# 12_CONSOLE.net
KiCad netlist of a schematic drawn in Altium Designer
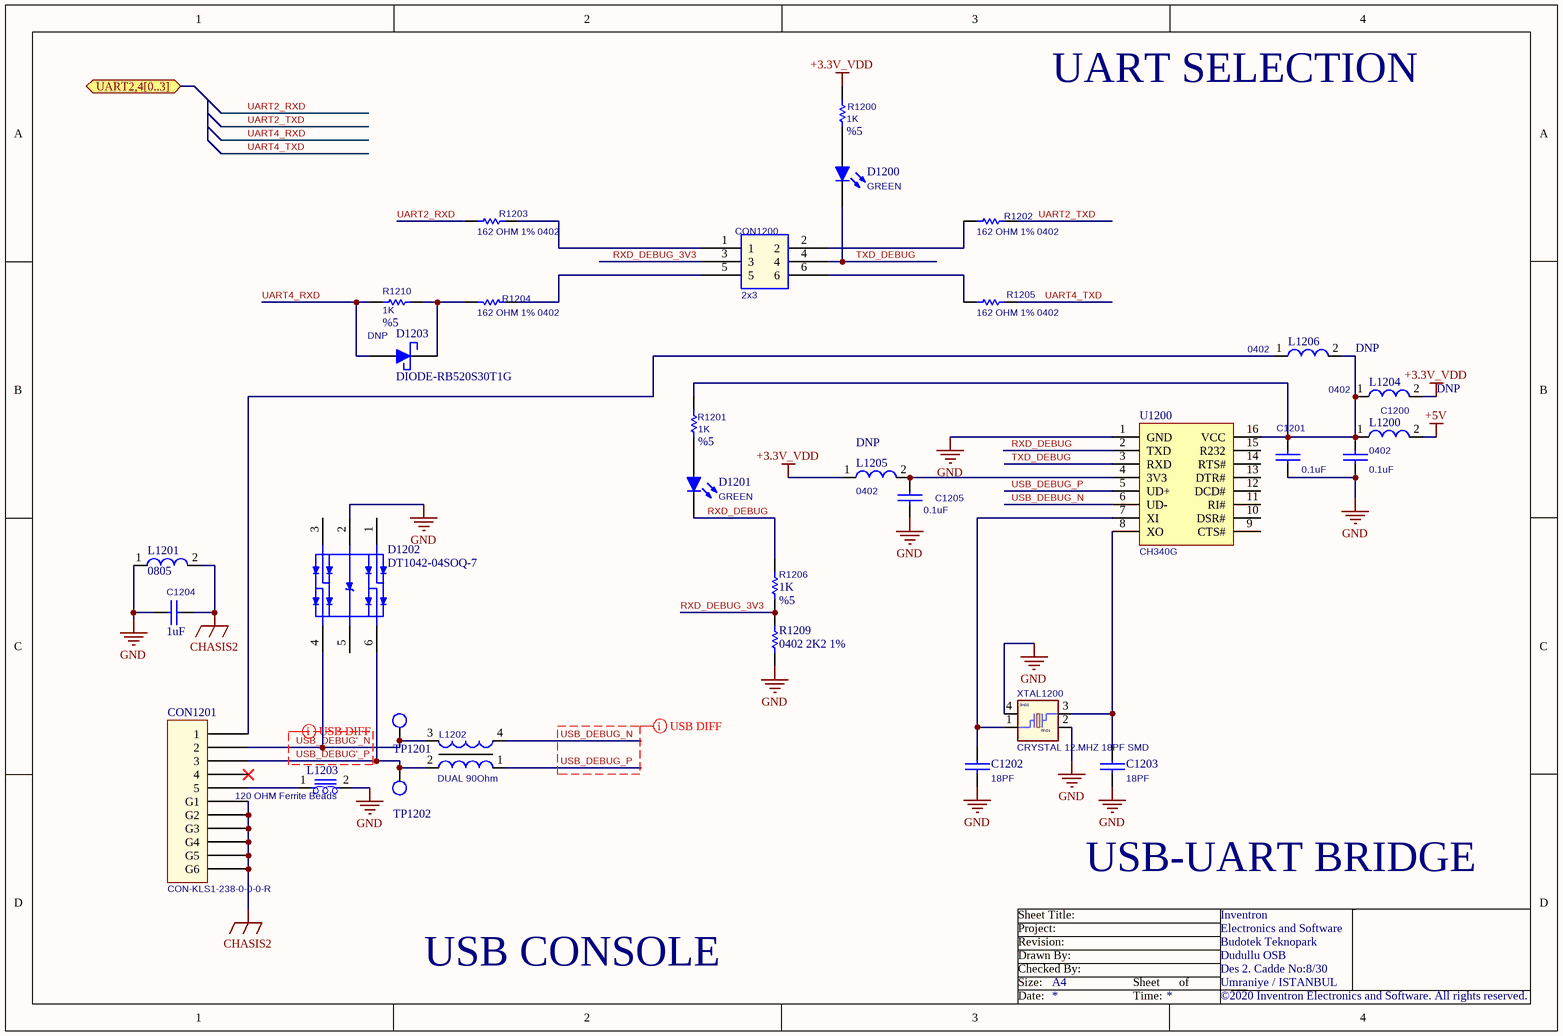
[diagram p0: 12 CONSOLE.SchDoc]

(export (version "E")
  (design (tool "Eeschema 10.0.6"))
  (components
    (comp (ref "C1200")
      (value "0.1uF")
      (footprint "0402_CC")
      (description "CAP VER 0.1UF 16V X7R 0402")
      (fields (field (name "CREATED BY") "LA") (field (name "CHECKED BY") "*"))
      (libsource (lib "ARETE_L") (part "CAP-CL05B104KO5NNNC"))
    )
    (comp (ref "C1201")
      (value "0.1uF")
      (footprint "0402_CC")
      (description "CAP VER 0.1UF 16V X7R 0402")
      (fields (field (name "CREATED BY") "LA") (field (name "CHECKED BY") "*"))
      (libsource (lib "ARETE_L") (part "CAP-CL05B104KO5NNNC"))
    )
    (comp (ref "C1202")
      (value "18PF")
      (footprint "0402_CC")
      (description "CAP CER 18PF 50V C0G/NP0 0402")
      (fields (field (name "CREATED BY") "*") (field (name "CHECKED BY") "*"))
      (libsource (lib "ARETE_SCH") (part "CAP-GCM1555C1H180JA16D"))
    )
    (comp (ref "C1203")
      (value "18PF")
      (footprint "0402_CC")
      (description "CAP CER 18PF 50V C0G/NP0 0402")
      (fields (field (name "CREATED BY") "*") (field (name "CHECKED BY") "*"))
      (libsource (lib "ARETE_SCH") (part "CAP-GCM1555C1H180JA16D"))
    )
    (comp (ref "C1204")
      (value "1uF")
      (footprint "0603_CC")
      (description "CAP CER 1UF 25V X7R 0603")
      (fields (field (name "CREATED BY") "LA") (field (name "CHECKED BY") "*"))
      (libsource (lib "ARETE_SCH") (part "CAP-CL10B105KA8NNNC"))
    )
    (comp (ref "C1205")
      (value "0.1uF")
      (footprint "0402_CC")
      (description "CAP VER 0.1UF 16V X7R 0402")
      (fields (field (name "CREATED BY") "LA") (field (name "CHECKED BY") "*"))
      (libsource (lib "ARETE_L") (part "CAP-CL05B104KO5NNNC"))
    )
    (comp (ref "CON1200")
      (value "2x3")
      (footprint "HEADER 2.54 X 3x2")
      (description "2x3 6 PIN 2.54MM HEADER")
      (fields (field (name "CREATED BY") "*") (field (name "CHECKED BY") "*"))
      (libsource (lib "ARETE_SCH") (part "CON-6 PIN 2.54MM"))
    )
    (comp (ref "CON1201")
      (value "CON-KLS1-238-0-0-0-R")
      (footprint "KLS1-238-0-0-0-R")
      (fields (field (name "CREATED BY") "OKS,EE") (field (name "CHECKED BY") "*"))
      (libsource (lib "ARETE_SCH") (part "CON-KLS1-238-0-0-0-R"))
    )
    (comp (ref "D1200")
      (value "GREEN")
      (footprint "0603_LED")
      (description "LED SMD 0603 SUPER GREEN")
      (fields (field (name "CREATED BY") "*") (field (name "CHECKED BY") "*"))
      (libsource (lib "ARETE_SCH") (part "LED-LTST-C190KRKT"))
    )
    (comp (ref "D1201")
      (value "GREEN")
      (footprint "0603_LED")
      (description "LED SMD 0603 SUPER GREEN")
      (fields (field (name "CREATED BY") "*") (field (name "CHECKED BY") "*"))
      (libsource (lib "ARETE_SCH") (part "LED-LTST-C190KRKT"))
    )
    (comp (ref "D1202")
      (value "DT1042-04SOQ-7")
      (footprint "DIODE-DT1042-04SOQ-7")
      (description "HDMI TVS DIODE")
      (fields (field (name "CREATED BY") "E.E") (field (name "CHECKED BY") "*"))
      (libsource (lib "ARETE_SCH") (part "DIODE-DT1042-04SOQ-7"))
    )
    (comp (ref "D1203")
      (value "DIODE-RB520S30T1G")
      (footprint "SOD523")
      (description "DIODE SCHOTTKY 30V 200MA SOD523")
      (fields (field (name "CREATED BY") "LA") (field (name "CHECKED BY") "*"))
      (libsource (lib "ARETE_L") (part "DIODE-RB520S30T1G"))
    )
    (comp (ref "L1200")
      (value "0402")
      (footprint "0402_RES")
      (description "0OHM 0402")
      (fields (field (name "CREATED BY") "EE") (field (name "CHECKED BY") "*"))
      (libsource (lib "ARETE_SCH") (part "IND-FERRITE (RES 0 OHM) 0402"))
    )
    (comp (ref "L1201")
      (value "0805")
      (footprint "0805")
      (description "0OHM 0805")
      (fields (field (name "CREATED BY") "EE") (field (name "CHECKED BY") "*"))
      (libsource (lib "ARETE_SCH") (part "IND-FERRITE (RES 0 OHM) 0805"))
    )
    (comp (ref "L1202")
      (value "DUAL 90Ohm")
      (footprint "DLW21H")
      (description "Common Mode Chokes Dual 90Ohm 100MHz 0.33A 0.35Ohm DCR SMD T/R")
      (fields (field (name "CREATED BY") "E.E") (field (name "CHECKED BY") "*"))
      (libsource (lib "ARETE_SCH") (part "IND-DLW21HN900SQ2L"))
    )
    (comp (ref "L1203")
      (value "120 OHM Ferrite Beads")
      (footprint "0603_RES")
      (description "Ferrite Beads Multi-Layer 120Ohm 25% 100MHz 2A 0.05Ohm DCR 0603 Automotive T/R")
      (fields (field (name "CREATED BY") "E.E") (field (name "CHECKED BY") "*"))
      (libsource (lib "ARETE_SCH") (part "IND-BLM18PG121SH1D"))
    )
    (comp (ref "L1204")
      (value "0402")
      (footprint "0402_RES")
      (description "0OHM 0402")
      (fields
        (field (name "ASSY_OPT") "DNP")
        (field (name "CREATED BY") "EE")
        (field (name "CHECKED BY") "*")
      )
      (libsource (lib "ARETE_SCH") (part "IND-FERRITE (RES 0 OHM) 0402"))
    )
    (comp (ref "L1205")
      (value "0402")
      (footprint "0402_RES")
      (description "0OHM 0402")
      (fields
        (field (name "ASSY_OPT") "DNP")
        (field (name "CREATED BY") "EE")
        (field (name "CHECKED BY") "*")
      )
      (libsource (lib "ARETE_SCH") (part "IND-FERRITE (RES 0 OHM) 0402"))
    )
    (comp (ref "L1206")
      (value "0402")
      (footprint "0402_RES")
      (description "0OHM 0402")
      (fields
        (field (name "ASSY_OPT") "DNP")
        (field (name "CREATED BY") "EE")
        (field (name "CHECKED BY") "*")
      )
      (libsource (lib "ARETE_SCH") (part "IND-FERRITE (RES 0 OHM) 0402"))
    )
    (comp (ref "R1200")
      (value "1K")
      (footprint "0402_RES")
      (description "RES 1K OHM 5% 1/16W 0402")
      (fields
        (field (name "TOLERANCE") "%5")
        (field (name "CREATED BY") "LA")
        (field (name "CHECKED BY") "*")
      )
      (libsource (lib "ARETE_SCH") (part "RES-RMCF0402JT1K00"))
    )
    (comp (ref "R1201")
      (value "1K")
      (footprint "0402_RES")
      (description "RES 1K OHM 5% 1/16W 0402")
      (fields
        (field (name "TOLERANCE") "%5")
        (field (name "CREATED BY") "LA")
        (field (name "CHECKED BY") "*")
      )
      (libsource (lib "ARETE_SCH") (part "RES-RMCF0402JT1K00"))
    )
    (comp (ref "R1202")
      (value "162 OHM 1% 0402")
      (footprint "0402_RES")
      (description "162 ±1% 0.1W, 1/10W Chip Resistor 0402 (1005 Metric) Automotive AEC-Q200 Thick Film")
      (fields (field (name "CREATED BY") "E.E") (field (name "CHECKED BY") "*"))
      (libsource (lib "ARETE_SCH") (part "RES-ERJ-2RKF1620X"))
    )
    (comp (ref "R1203")
      (value "162 OHM 1% 0402")
      (footprint "0402_RES")
      (description "162 ±1% 0.1W, 1/10W Chip Resistor 0402 (1005 Metric) Automotive AEC-Q200 Thick Film")
      (fields (field (name "CREATED BY") "E.E") (field (name "CHECKED BY") "*"))
      (libsource (lib "ARETE_SCH") (part "RES-ERJ-2RKF1620X"))
    )
    (comp (ref "R1204")
      (value "162 OHM 1% 0402")
      (footprint "0402_RES")
      (description "162 ±1% 0.1W, 1/10W Chip Resistor 0402 (1005 Metric) Automotive AEC-Q200 Thick Film")
      (fields (field (name "CREATED BY") "E.E") (field (name "CHECKED BY") "*"))
      (libsource (lib "ARETE_SCH") (part "RES-ERJ-2RKF1620X"))
    )
    (comp (ref "R1205")
      (value "162 OHM 1% 0402")
      (footprint "0402_RES")
      (description "162 ±1% 0.1W, 1/10W Chip Resistor 0402 (1005 Metric) Automotive AEC-Q200 Thick Film")
      (fields (field (name "CREATED BY") "E.E") (field (name "CHECKED BY") "*"))
      (libsource (lib "ARETE_SCH") (part "RES-ERJ-2RKF1620X"))
    )
    (comp (ref "R1206")
      (value "1K")
      (footprint "0402_RES")
      (description "RES 1K OHM 5% 1/16W 0402")
      (fields
        (field (name "TOLERANCE") "%5")
        (field (name "CREATED BY") "LA")
        (field (name "CHECKED BY") "*")
      )
      (libsource (lib "ARETE_SCH") (part "RES-RMCF0402JT1K00"))
    )
    (comp (ref "R1209")
      (value "0402 2K2 1%")
      (footprint "0402_RES")
      (fields (field (name "CREATED BY") "E.E") (field (name "CHECKED BY") "*"))
      (libsource (lib "ARETE_V2_SCH") (part "RES-CRGCQ0402F2K2"))
    )
    (comp (ref "R1210")
      (value "1K")
      (footprint "0402_RES")
      (description "RES 1K OHM 5% 1/16W 0402")
      (fields
        (field (name "ASSY_OPT") "DNP")
        (field (name "TOLERANCE") "%5")
        (field (name "CREATED BY") "LA")
        (field (name "CHECKED BY") "*")
      )
      (libsource (lib "ARETE_SCH") (part "RES-RMCF0402JT1K00"))
    )
    (comp (ref "TP1201")
      (value "TEST POINT 15")
      (footprint "testpoint_15")
      (libsource (lib "ARETE_L") (part "TEST POINT 15"))
    )
    (comp (ref "TP1202")
      (value "TEST POINT 15")
      (footprint "testpoint_15")
      (libsource (lib "ARETE_L") (part "TEST POINT 15"))
    )
    (comp (ref "U1200")
      (value "CH340G")
      (footprint "CH340G")
      (description "IC-340 USB INTERFACE SO16")
      (fields (field (name "CREATED BY") "E.E.") (field (name "CHECKED BY") "*"))
      (libsource (lib "ARETE_SCH") (part "IC-CH340G"))
    )
    (comp (ref "XTAL1200")
      (value "CRYSTAL 12.MHZ 18PF SMD")
      (footprint "XTLOSC4_3P2X2P5MM_SM")
      (description "CRYSTAL 12.0000MHZ 18PF SMD")
      (fields (field (name "CREATED BY") "E.E") (field (name "CHECKED BY") "*"))
      (libsource (lib "ARETE_SCH") (part "XTAL-FA-238V 12.0000MB50X-C0"))
    )
  )
  (nets
    (net (code "5") (name "+3.3V_VDD") (class "Default")
      (node (ref "L1204") (pin "2") (pinfunction "2_2") (pintype "passive"))
      (node (ref "L1205") (pin "1") (pinfunction "1_1") (pintype "passive"))
      (node (ref "R1200") (pin "1") (pinfunction "1_1") (pintype "passive"))
    )
    (net (code "6") (name "+5V") (class "Default")
      (node (ref "L1200") (pin "2") (pinfunction "2_2") (pintype "passive"))
    )
    (net (code "7") (name "/RXD_DEBUG") (class "Default")
      (node (ref "D1201") (pin "2") (pinfunction "K_2") (pintype "passive"))
      (node (ref "R1206") (pin "2") (pinfunction "2_2") (pintype "passive"))
      (node (ref "U1200") (pin "2") (pinfunction "TXD_2") (pintype "passive"))
    )
    (net (code "8") (name "/RXD_DEBUG_3V3") (class "Default")
      (node (ref "CON1200") (pin "3") (pinfunction "3_3") (pintype "passive"))
      (node (ref "R1206") (pin "1") (pinfunction "1_1") (pintype "passive"))
      (node (ref "R1209") (pin "2") (pinfunction "2_2") (pintype "passive"))
    )
    (net (code "9") (name "/TXD_DEBUG") (class "Default")
      (node (ref "CON1200") (pin "4") (pinfunction "4_4") (pintype "passive"))
      (node (ref "D1200") (pin "2") (pinfunction "K_2") (pintype "passive"))
      (node (ref "U1200") (pin "3") (pinfunction "RXD_3") (pintype "passive"))
    )
    (net (code "11") (name "/UART2_RXD") (class "Default")
      (node (ref "R1203") (pin "1") (pinfunction "1_1") (pintype "passive"))
    )
    (net (code "12") (name "/UART2_TXD") (class "Default")
      (node (ref "R1202") (pin "2") (pinfunction "2_2") (pintype "passive"))
    )
    (net (code "13") (name "/UART4_RXD") (class "Default")
      (node (ref "D1203") (pin "1") (pinfunction "A_1") (pintype "passive"))
      (node (ref "R1210") (pin "1") (pinfunction "1_1") (pintype "passive"))
    )
    (net (code "14") (name "/UART4_TXD") (class "Default")
      (node (ref "R1205") (pin "2") (pinfunction "2_2") (pintype "passive"))
    )
    (net (code "15") (name "/USB_DEBUG'_N") (class "Default")
      (node (ref "CON1201") (pin "2") (pinfunction "2_2") (pintype "passive"))
      (node (ref "D1202") (pin "4") (pinfunction "IO3_4") (pintype "passive"))
      (node (ref "L1202") (pin "3") (pinfunction "3_3") (pintype "passive"))
      (node (ref "TP1201") (pin "1") (pinfunction "1_1") (pintype "passive"))
    )
    (net (code "16") (name "/USB_DEBUG'_P") (class "Default")
      (node (ref "CON1201") (pin "3") (pinfunction "3_3") (pintype "passive"))
      (node (ref "D1202") (pin "6") (pinfunction "IO4_6") (pintype "passive"))
      (node (ref "L1202") (pin "2") (pinfunction "2_2") (pintype "passive"))
      (node (ref "TP1202") (pin "1") (pinfunction "1_1") (pintype "passive"))
    )
    (net (code "17") (name "/USB_DEBUG_N") (class "Default")
      (node (ref "L1202") (pin "4") (pinfunction "4_4") (pintype "passive"))
      (node (ref "U1200") (pin "6") (pinfunction "UD-_6") (pintype "passive"))
    )
    (net (code "18") (name "/USB_DEBUG_P") (class "Default")
      (node (ref "L1202") (pin "1") (pinfunction "1_1") (pintype "passive"))
      (node (ref "U1200") (pin "5") (pinfunction "UD+_5") (pintype "passive"))
    )
    (net (code "19") (name "CHASIS2") (class "Default")
      (node (ref "C1204") (pin "1") (pinfunction "1_1") (pintype "passive"))
      (node (ref "CON1201") (pin "G1") (pinfunction "G1_G1") (pintype "passive"))
      (node (ref "CON1201") (pin "G2") (pinfunction "G2_G2") (pintype "passive"))
      (node (ref "CON1201") (pin "G3") (pinfunction "G3_G3") (pintype "passive"))
      (node (ref "CON1201") (pin "G4") (pinfunction "G4_G4") (pintype "passive"))
      (node (ref "CON1201") (pin "G5") (pinfunction "G5_G5") (pintype "passive"))
      (node (ref "CON1201") (pin "G6") (pinfunction "G6_G6") (pintype "passive"))
      (node (ref "L1201") (pin "2") (pinfunction "2_2") (pintype "passive"))
    )
    (net (code "20") (name "GND") (class "Default")
      (node (ref "C1200") (pin "2") (pinfunction "2_2") (pintype "passive"))
      (node (ref "C1201") (pin "2") (pinfunction "2_2") (pintype "passive"))
      (node (ref "C1202") (pin "2") (pinfunction "2_2") (pintype "passive"))
      (node (ref "C1203") (pin "2") (pinfunction "2_2") (pintype "passive"))
      (node (ref "C1204") (pin "2") (pinfunction "2_2") (pintype "passive"))
      (node (ref "C1205") (pin "2") (pinfunction "2_2") (pintype "passive"))
      (node (ref "D1202") (pin "2") (pinfunction "VSS_2") (pintype "power_in"))
      (node (ref "L1201") (pin "1") (pinfunction "1_1") (pintype "passive"))
      (node (ref "L1203") (pin "2") (pinfunction "2_2") (pintype "passive"))
      (node (ref "R1209") (pin "1") (pinfunction "1_1") (pintype "passive"))
      (node (ref "U1200") (pin "1") (pinfunction "GND_1") (pintype "passive"))
      (node (ref "XTAL1200") (pin "2") (pinfunction "GND1_2") (pintype "power_in"))
      (node (ref "XTAL1200") (pin "4") (pinfunction "GND2_4") (pintype "power_in"))
    )
    (net (code "21") (name "Net-(CON1200-Pad1)") (class "Default")
      (node (ref "CON1200") (pin "1") (pinfunction "1_1") (pintype "passive"))
      (node (ref "R1203") (pin "2") (pinfunction "2_2") (pintype "passive"))
    )
    (net (code "22") (name "Net-(CON1200-Pad2)") (class "Default")
      (node (ref "CON1200") (pin "2") (pinfunction "2_2") (pintype "passive"))
      (node (ref "R1202") (pin "1") (pinfunction "1_1") (pintype "passive"))
    )
    (net (code "23") (name "Net-(CON1200-Pad5)") (class "Default")
      (node (ref "CON1200") (pin "5") (pinfunction "5_5") (pintype "passive"))
      (node (ref "R1204") (pin "2") (pinfunction "2_2") (pintype "passive"))
    )
    (net (code "24") (name "Net-(CON1200-Pad6)") (class "Default")
      (node (ref "CON1200") (pin "6") (pinfunction "6_6") (pintype "passive"))
      (node (ref "R1205") (pin "1") (pinfunction "1_1") (pintype "passive"))
    )
    (net (code "25") (name "Net-(CON1201-Pad1)") (class "Default")
      (node (ref "CON1201") (pin "1") (pinfunction "1_1") (pintype "passive"))
      (node (ref "L1206") (pin "1") (pinfunction "1_1") (pintype "passive"))
    )
    (net (code "26") (name "Net-(CON1201-Pad5)") (class "Default")
      (node (ref "CON1201") (pin "5") (pinfunction "5_5") (pintype "passive"))
      (node (ref "L1203") (pin "1") (pinfunction "1_1") (pintype "passive"))
    )
    (net (code "27") (name "Net-(D1200-A)") (class "Default")
      (node (ref "D1200") (pin "1") (pinfunction "A_1") (pintype "passive"))
      (node (ref "R1200") (pin "2") (pinfunction "2_2") (pintype "passive"))
    )
    (net (code "28") (name "Net-(D1201-A)") (class "Default")
      (node (ref "D1201") (pin "1") (pinfunction "A_1") (pintype "passive"))
      (node (ref "R1201") (pin "2") (pinfunction "2_2") (pintype "passive"))
    )
    (net (code "29") (name "Net-(D1203-K)") (class "Default")
      (node (ref "D1203") (pin "2") (pinfunction "K_2") (pintype "passive"))
      (node (ref "R1204") (pin "1") (pinfunction "1_1") (pintype "passive"))
      (node (ref "R1210") (pin "2") (pinfunction "2_2") (pintype "passive"))
    )
    (net (code "30") (name "Net-(U1200-3V3)") (class "Default")
      (node (ref "C1205") (pin "1") (pinfunction "1_1") (pintype "passive"))
      (node (ref "L1205") (pin "2") (pinfunction "2_2") (pintype "passive"))
      (node (ref "U1200") (pin "4") (pinfunction "3V3_4") (pintype "passive"))
    )
    (net (code "31") (name "Net-(U1200-VCC)") (class "Default")
      (node (ref "C1200") (pin "1") (pinfunction "1_1") (pintype "passive"))
      (node (ref "C1201") (pin "1") (pinfunction "1_1") (pintype "passive"))
      (node (ref "L1200") (pin "1") (pinfunction "1_1") (pintype "passive"))
      (node (ref "L1204") (pin "1") (pinfunction "1_1") (pintype "passive"))
      (node (ref "L1206") (pin "2") (pinfunction "2_2") (pintype "passive"))
      (node (ref "R1201") (pin "1") (pinfunction "1_1") (pintype "passive"))
      (node (ref "U1200") (pin "16") (pinfunction "VCC_16") (pintype "passive"))
    )
    (net (code "32") (name "Net-(U1200-XI)") (class "Default")
      (node (ref "C1202") (pin "1") (pinfunction "1_1") (pintype "passive"))
      (node (ref "U1200") (pin "7") (pinfunction "XI_7") (pintype "passive"))
      (node (ref "XTAL1200") (pin "1") (pinfunction "1_1") (pintype "passive"))
    )
    (net (code "33") (name "Net-(U1200-XO)") (class "Default")
      (node (ref "C1203") (pin "1") (pinfunction "1_1") (pintype "passive"))
      (node (ref "U1200") (pin "8") (pinfunction "XO_8") (pintype "passive"))
      (node (ref "XTAL1200") (pin "3") (pinfunction "3_3") (pintype "passive"))
    )
    (net (code "34") (name "unconnected-(CON1201-Pad4)") (class "Default")
      (node (ref "CON1201") (pin "4") (pinfunction "4_4") (pintype "passive+no_connect"))
    )
    (net (code "35") (name "unconnected-(D1202-IO1-Pad1)") (class "Default")
      (node (ref "D1202") (pin "1") (pinfunction "IO1_1") (pintype "passive"))
    )
    (net (code "36") (name "unconnected-(D1202-IO2-Pad3)") (class "Default")
      (node (ref "D1202") (pin "3") (pinfunction "IO2_3") (pintype "passive"))
    )
    (net (code "37") (name "unconnected-(D1202-VCC-Pad5)") (class "Default")
      (node (ref "D1202") (pin "5") (pinfunction "VCC_5") (pintype "power_in"))
    )
    (net (code "38") (name "unconnected-(U1200-CTS#-Pad9)") (class "Default")
      (node (ref "U1200") (pin "9") (pinfunction "CTS#_9") (pintype "passive"))
    )
    (net (code "39") (name "unconnected-(U1200-DCD#-Pad12)") (class "Default")
      (node (ref "U1200") (pin "12") (pinfunction "DCD#_12") (pintype "passive"))
    )
    (net (code "40") (name "unconnected-(U1200-DSR#-Pad10)") (class "Default")
      (node (ref "U1200") (pin "10") (pinfunction "DSR#_10") (pintype "passive"))
    )
    (net (code "41") (name "unconnected-(U1200-DTR#-Pad13)") (class "Default")
      (node (ref "U1200") (pin "13") (pinfunction "DTR#_13") (pintype "passive"))
    )
    (net (code "42") (name "unconnected-(U1200-R232-Pad15)") (class "Default")
      (node (ref "U1200") (pin "15") (pinfunction "R232_15") (pintype "passive"))
    )
    (net (code "43") (name "unconnected-(U1200-RI#-Pad11)") (class "Default")
      (node (ref "U1200") (pin "11") (pinfunction "RI#_11") (pintype "passive"))
    )
    (net (code "44") (name "unconnected-(U1200-RTS#-Pad14)") (class "Default")
      (node (ref "U1200") (pin "14") (pinfunction "RTS#_14") (pintype "passive"))
    )
  )
)
